# Multivibrador.net
KiCad netlist of a schematic drawn in Altium Designer
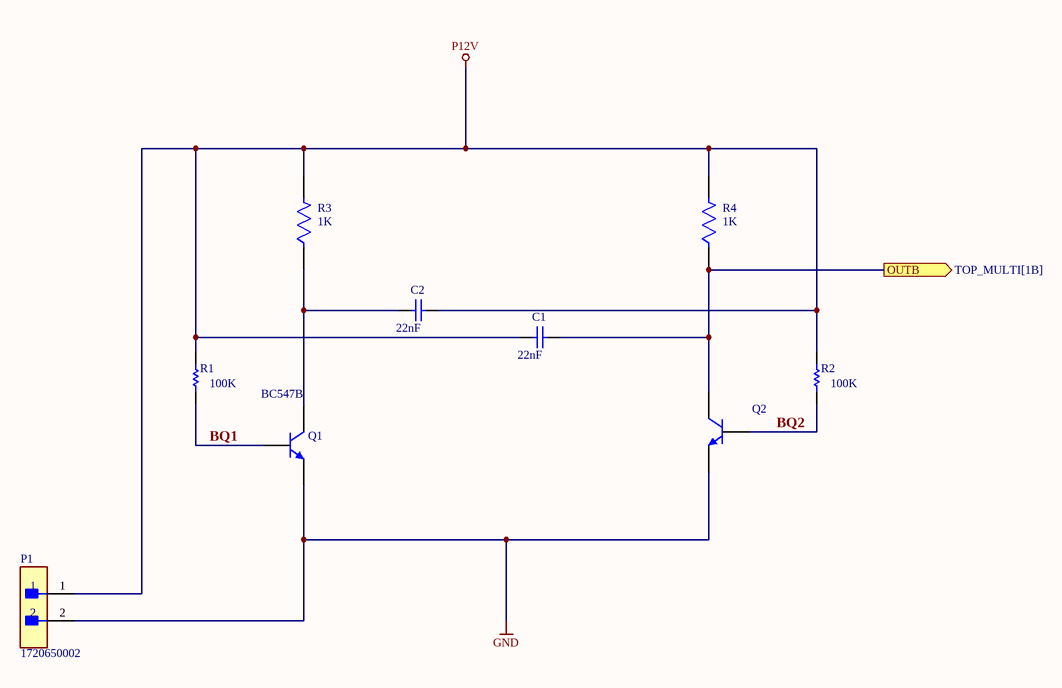
[diagram p0: Multivibrador.SchDoc]

(export (version "E")
  (design (tool "Eeschema 10.0.6"))
  (components
    (comp (ref "C1")
      (value "22nF")
      (footprint "CAPC1608X90X35ML10T15")
      (fields (field (name "MANUFACTURER") "Murata") (field (name "PART NUMBER") "GRM188R71H223KA01D"))
      (libsource (lib "Altium Content Vault") (part "CAP"))
    )
    (comp (ref "C2")
      (value "22nF")
      (footprint "CAPC1608X90X35ML10T15")
      (fields (field (name "MANUFACTURER") "Murata") (field (name "PART NUMBER") "GRM188R71H223KA01D"))
      (libsource (lib "Altium Content Vault") (part "CAP"))
    )
    (comp (ref "P1")
      (value "1720650002")
      (footprint "FP-1720650002-MFG")
      (description "CONNECTOR, HEADER, 2POS, 2ROW")
      (fields (field (name "OCTOPART") "https://octopart.com/172065-0002-molex-34473111"))
      (libsource (lib "Altium Content Vault") (part "3bc925449376181038e59eaffc5286c"))
    )
    (comp (ref "Q1")
      (value "BC547B")
      (footprint "ONSC-TO-92-3-29-11")
      (description "Trans GP BJT NPN 45V 0.1A 500mW Automotive 3-Pin TO-92 Ammo")
      (fields
        (field (name "MANUFACTURER") "On Semiconductor")
        (field (name "SUPPLIER PART NUMBER 1") "BC547B")
      )
      (libsource (lib "Altium Content Vault") (part "ONSC-NPN-C1B2E3-3"))
    )
    (comp (ref "Q2")
      (value "BC547B")
      (footprint "ONSC-TO-92-3-29-11")
      (description "Trans GP BJT NPN 45V 0.1A 500mW Automotive 3-Pin TO-92 Ammo")
      (fields (field (name "MANUFACTURER") "On Semiconductor"))
      (libsource (lib "Altium Content Vault") (part "ONSC-NPN-C1B2E3-3"))
    )
    (comp (ref "R1")
      (value "100K")
      (footprint "RESC2013X50X30NL20T20")
      (fields (field (name "MANUFACTURER") "Vishay Dale") (field (name "PART NUMBER") "CRCW0805100KJNEA"))
      (libsource (lib "Altium Content Vault") (part "RES"))
    )
    (comp (ref "R2")
      (value "100K")
      (footprint "RESC2013X50X30NL20T20")
      (fields (field (name "MANUFACTURER") "Vishay Dale") (field (name "PART NUMBER") "CRCW0805100KJNEA"))
      (libsource (lib "Altium Content Vault") (part "RES"))
    )
    (comp (ref "R3")
      (value "1K")
      (footprint "FP-ESR03-MFG")
      (description "1kΩ ±5% 0.25W 0603 Anti-Surge Chip Resistor AEC-Q200")
      (fields (field (name "TOLERANCE") "5%") (field (name "Comment") "ESR03EZPJ102"))
      (libsource (lib "Altium Content Vault") (part "1029c3af85768c4190bb7ad29bc67b5"))
    )
    (comp (ref "R4")
      (value "1K")
      (footprint "FP-ESR03-MFG")
      (description "1kΩ ±5% 0.25W 0603 Anti-Surge Chip Resistor AEC-Q200")
      (fields (field (name "TOLERANCE") "5%") (field (name "Comment") "ESR03EZPJ102"))
      (libsource (lib "Altium Content Vault") (part "1029c3af85768c4190bb7ad29bc67b5"))
    )
  )
  (nets
    (net (code "1") (name "/BQ1") (class "Default")
      (node (ref "Q1") (pin "2") (pinfunction "B_2") (pintype "passive"))
      (node (ref "R1") (pin "1") (pinfunction "1_1") (pintype "passive"))
    )
    (net (code "2") (name "/BQ2") (class "Default")
      (node (ref "Q2") (pin "2") (pinfunction "B_2") (pintype "passive"))
      (node (ref "R2") (pin "1") (pinfunction "1_1") (pintype "passive"))
    )
    (net (code "3") (name "/OUTB") (class "Default")
      (node (ref "C1") (pin "1") (pinfunction "1_1") (pintype "passive"))
      (node (ref "Q2") (pin "1") (pinfunction "C_1") (pintype "passive"))
      (node (ref "R4") (pin "1") (pinfunction "1_1") (pintype "passive"))
    )
    (net (code "4") (name "GND") (class "Default")
      (node (ref "P1") (pin "2") (pinfunction "2_2") (pintype "passive"))
      (node (ref "Q1") (pin "3") (pinfunction "E_3") (pintype "passive"))
      (node (ref "Q2") (pin "3") (pinfunction "E_3") (pintype "passive"))
    )
    (net (code "5") (name "Net-(Q1-C)") (class "Default")
      (node (ref "C2") (pin "2") (pinfunction "2_2") (pintype "passive"))
      (node (ref "Q1") (pin "1") (pinfunction "C_1") (pintype "passive"))
      (node (ref "R3") (pin "1") (pinfunction "1_1") (pintype "passive"))
    )
    (net (code "6") (name "P12V") (class "Default")
      (node (ref "C1") (pin "2") (pinfunction "2_2") (pintype "passive"))
      (node (ref "C2") (pin "1") (pinfunction "1_1") (pintype "passive"))
      (node (ref "P1") (pin "1") (pinfunction "1_1") (pintype "passive"))
      (node (ref "R1") (pin "2") (pinfunction "2_2") (pintype "passive"))
      (node (ref "R2") (pin "2") (pinfunction "2_2") (pintype "passive"))
      (node (ref "R3") (pin "2") (pinfunction "2_2") (pintype "passive"))
      (node (ref "R4") (pin "2") (pinfunction "2_2") (pintype "passive"))
    )
  )
)
